# Mi2.net
KiCad netlist of a schematic drawn in EAGLE
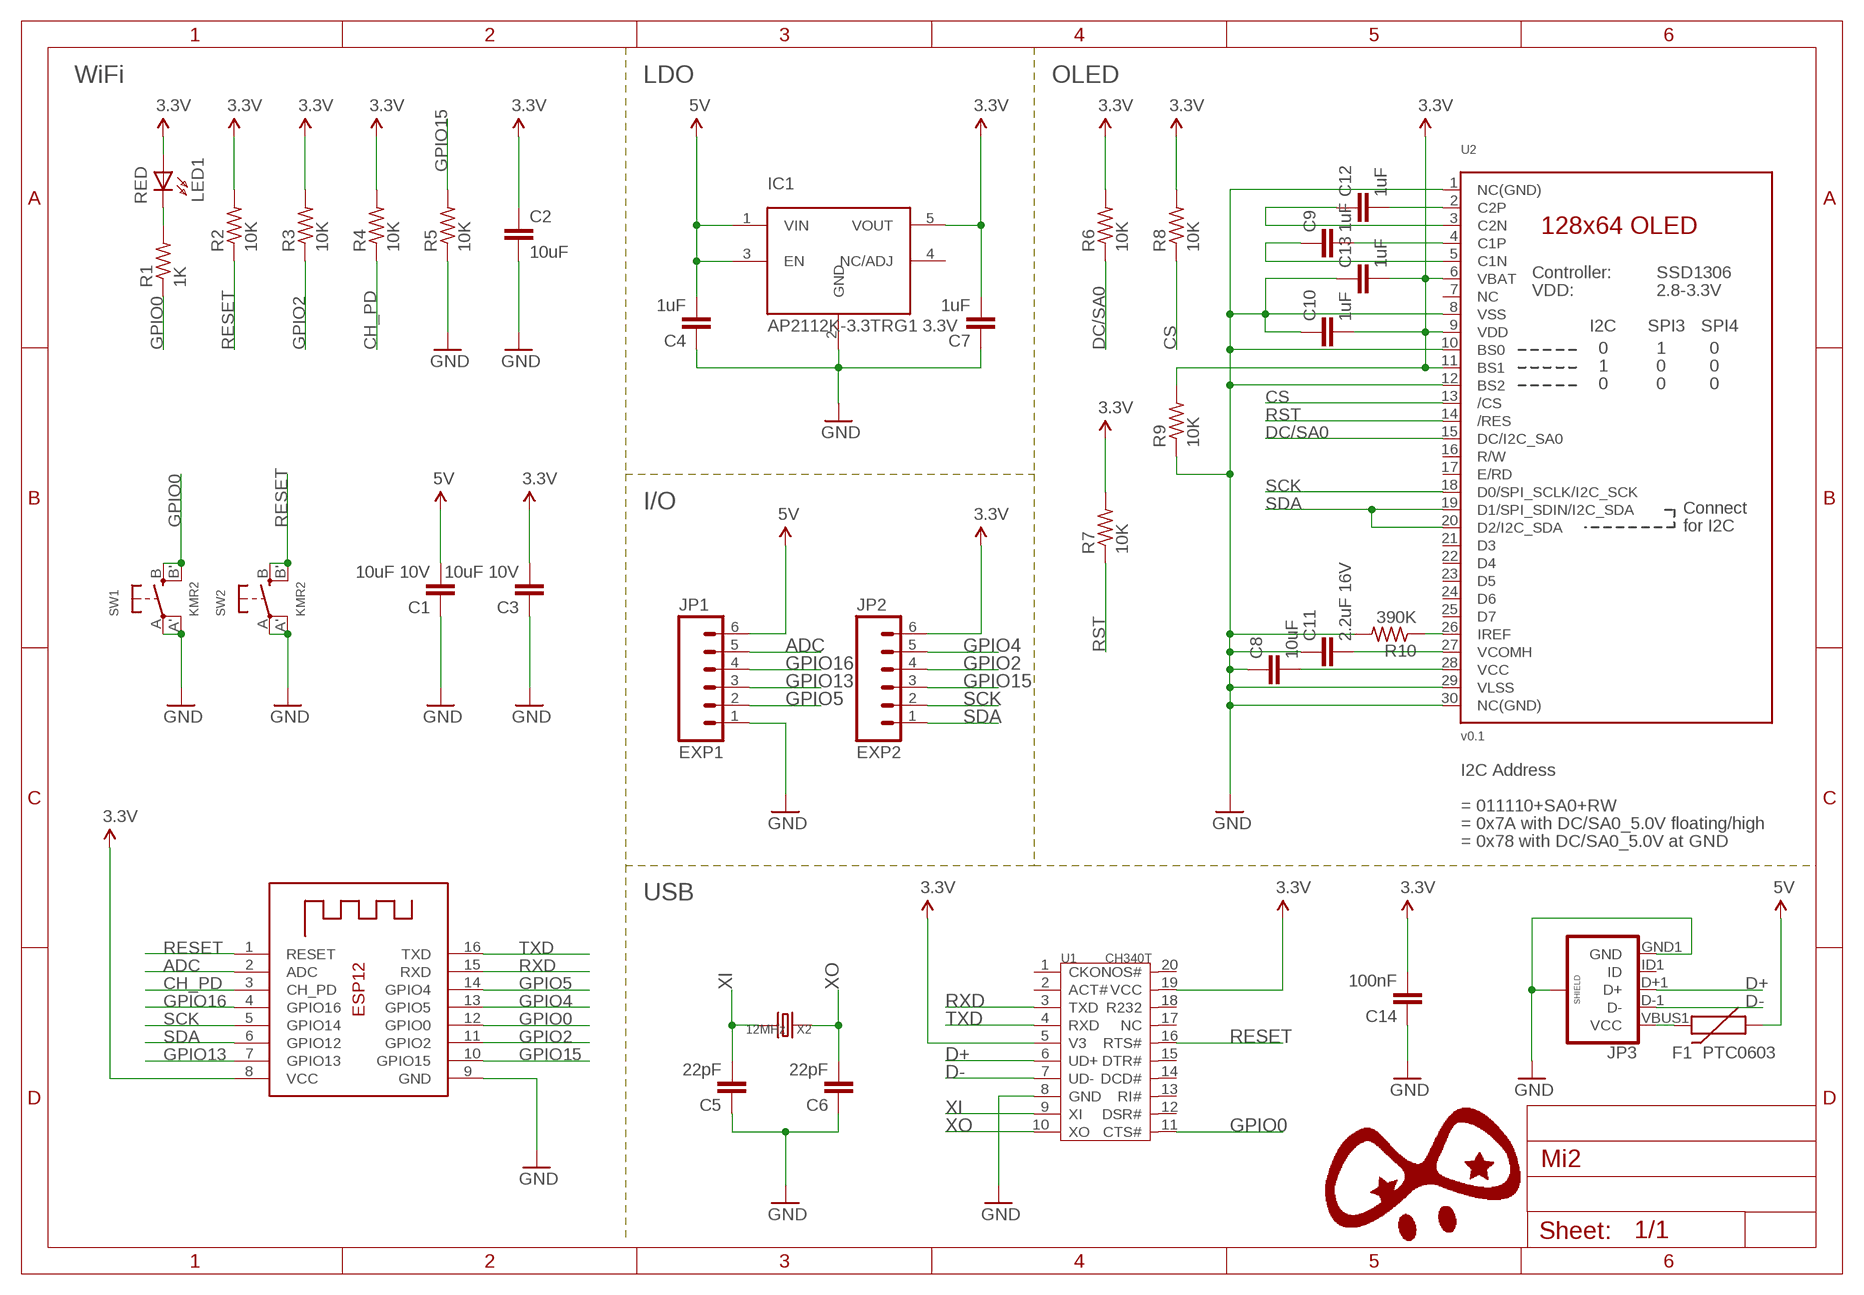
[diagram p0: schematic, sheet 1]

(export (version "E")
  (design (tool "Eeschema 10.0.6"))
  (components
    (comp (ref "C1")
      (value "10uF 10V")
      (footprint "eagle-import:0402-CAP")
      (libsource (lib "eagle-import") (part "CAP0402-CAP"))
    )
    (comp (ref "C2")
      (value "10uF")
      (footprint "eagle-import:0603-CAP")
      (libsource (lib "eagle-import") (part "10UF-6.3V-20%(0603)"))
    )
    (comp (ref "C3")
      (value "10uF 10V")
      (footprint "eagle-import:0402-CAP")
      (libsource (lib "eagle-import") (part "CAP0402-CAP"))
    )
    (comp (ref "C4")
      (value "1uF")
      (footprint "eagle-import:0402-CAP")
      (libsource (lib "eagle-import") (part "CAP0402-CAP"))
    )
    (comp (ref "C5")
      (value "22pF")
      (footprint "eagle-import:0402-CAP")
      (libsource (lib "eagle-import") (part "CAP0402-CAP"))
    )
    (comp (ref "C6")
      (value "22pF")
      (footprint "eagle-import:0402-CAP")
      (libsource (lib "eagle-import") (part "CAP0402-CAP"))
    )
    (comp (ref "C7")
      (value "1uF")
      (footprint "eagle-import:0402-CAP")
      (libsource (lib "eagle-import") (part "CAP0402-CAP"))
    )
    (comp (ref "C8")
      (value "10uF")
      (footprint "eagle-import:0603-CAP")
      (libsource (lib "eagle-import") (part "10UF-6.3V-20%(0603)"))
    )
    (comp (ref "C9")
      (value "1uF")
      (footprint "eagle-import:0603-CAP")
      (libsource (lib "eagle-import") (part "10UF-6.3V-20%(0603)"))
    )
    (comp (ref "C10")
      (value "1uF")
      (footprint "eagle-import:0603-CAP")
      (libsource (lib "eagle-import") (part "10UF-6.3V-20%(0603)"))
    )
    (comp (ref "C11")
      (value "2.2uF 16V")
      (footprint "eagle-import:0603-CAP")
      (libsource (lib "eagle-import") (part "10UF-6.3V-20%(0603)"))
    )
    (comp (ref "C12")
      (value "1uF")
      (footprint "eagle-import:0603-CAP")
      (libsource (lib "eagle-import") (part "10UF-6.3V-20%(0603)"))
    )
    (comp (ref "C13")
      (value "1uF")
      (footprint "eagle-import:0603-CAP")
      (libsource (lib "eagle-import") (part "10UF-6.3V-20%(0603)"))
    )
    (comp (ref "C14")
      (value "100nF")
      (footprint "eagle-import:0402-CAP")
      (libsource (lib "eagle-import") (part "CAP0402-CAP"))
    )
    (comp (ref "F1")
      (value "PTC0603")
      (footprint "eagle-import:0603")
      (libsource (lib "eagle-import") (part "PTC0603"))
    )
    (comp (ref "IC1")
      (value "AP2112K-3.3TRG1 3.3V")
      (footprint "eagle-import:SOT23-5")
      (libsource (lib "eagle-import") (part "5PIN_REG"))
    )
    (comp (ref "JP1")
      (value "EXP1")
      (footprint "eagle-import:1X06_LOCK")
      (libsource (lib "eagle-import") (part "M06LOCK"))
    )
    (comp (ref "JP2")
      (value "EXP2")
      (footprint "eagle-import:1X06_LOCK")
      (libsource (lib "eagle-import") (part "M06LOCK"))
    )
    (comp (ref "JP3")
      (value "USB_MICROB_PLUGCONN-11752")
      (footprint "eagle-import:USB-B-MICRO-SMD_V03")
      (libsource (lib "eagle-import") (part "USB_MICROB_PLUGCONN-11752"))
    )
    (comp (ref "LED1")
      (value "RED")
      (footprint "eagle-import:LED-0603_L")
      (libsource (lib "eagle-import") (part "LED0603DWS_L"))
    )
    (comp (ref "R1")
      (value "1K")
      (footprint "eagle-import:R0402")
      (libsource (lib "eagle-import") (part "R-US_R0402"))
    )
    (comp (ref "R2")
      (value "10K")
      (footprint "eagle-import:R0402")
      (libsource (lib "eagle-import") (part "R-US_R0402"))
    )
    (comp (ref "R3")
      (value "10K")
      (footprint "eagle-import:R0402")
      (libsource (lib "eagle-import") (part "R-US_R0402"))
    )
    (comp (ref "R4")
      (value "10K")
      (footprint "eagle-import:R0402")
      (libsource (lib "eagle-import") (part "R-US_R0402"))
    )
    (comp (ref "R5")
      (value "10K")
      (footprint "eagle-import:R0402")
      (libsource (lib "eagle-import") (part "R-US_R0402"))
    )
    (comp (ref "R6")
      (value "10K")
      (footprint "eagle-import:R0402")
      (libsource (lib "eagle-import") (part "R-US_R0402"))
    )
    (comp (ref "R7")
      (value "10K")
      (footprint "eagle-import:R0402")
      (libsource (lib "eagle-import") (part "R-US_R0402"))
    )
    (comp (ref "R8")
      (value "10K")
      (footprint "eagle-import:R0402")
      (libsource (lib "eagle-import") (part "R-US_R0402"))
    )
    (comp (ref "R9")
      (value "10K")
      (footprint "eagle-import:R0402")
      (libsource (lib "eagle-import") (part "R-US_R0402"))
    )
    (comp (ref "R10")
      (value "390K")
      (footprint "eagle-import:R0402")
      (libsource (lib "eagle-import") (part "R-US_R0402"))
    )
    (comp (ref "SW1")
      (value "KMR2")
      (footprint "eagle-import:BTN_KMR2_4.6X2.8")
      (libsource (lib "eagle-import") (part "SWITCH_TACT_SMT4.6X2.8"))
    )
    (comp (ref "SW2")
      (value "KMR2")
      (footprint "eagle-import:BTN_KMR2_4.6X2.8")
      (libsource (lib "eagle-import") (part "SWITCH_TACT_SMT4.6X2.8"))
    )
    (comp (ref "U1")
      (value "CH340T")
      (footprint "eagle-import:SSOP20")
      (libsource (lib "eagle-import") (part "CH340T"))
    )
    (comp (ref "U2")
      (value "v0.1")
      (footprint "eagle-import:UG-2864HSWEG01_0.96IN_WRAPAROUND")
      (libsource (lib "eagle-import") (part "DISP_OLED_UG-2864HSWEG010.96{dblquote}"))
    )
    (comp (ref "X1")
      (value "ESP-12")
      (footprint "eagle-import:ESP-12")
      (libsource (lib "eagle-import") (part "ESP-12"))
    )
    (comp (ref "X2")
      (value "12MHz")
      (footprint "eagle-import:2P-SMD-5X3.2")
      (libsource (lib "eagle-import") (part "CRYSTAL'5032'"))
    )
  )
  (nets
    (net (code "1") (name "/ADC") (class "Default")
      (node (ref "JP1") (pin "5") (pinfunction "5_5") (pintype "passive"))
      (node (ref "X1") (pin "2") (pinfunction "ADC_2") (pintype "passive"))
    )
    (net (code "2") (name "/CH_PD") (class "Default")
      (node (ref "R4") (pin "1") (pinfunction "1_1") (pintype "passive"))
      (node (ref "X1") (pin "3") (pinfunction "CH_PD_3") (pintype "input"))
    )
    (net (code "3") (name "/CS") (class "Default")
      (node (ref "R8") (pin "1") (pinfunction "1_1") (pintype "passive"))
      (node (ref "U2") (pin "13") (pinfunction "/CS_13") (pintype "input"))
    )
    (net (code "4") (name "/D+") (class "Default")
      (node (ref "JP3") (pin "D+1") (pinfunction "D+_D+1") (pintype "bidirectional"))
      (node (ref "U1") (pin "6") (pinfunction "UD+_6") (pintype "bidirectional"))
    )
    (net (code "5") (name "/D-") (class "Default")
      (node (ref "JP3") (pin "D-1") (pinfunction "D-_D-1") (pintype "bidirectional"))
      (node (ref "U1") (pin "7") (pinfunction "UD-_7") (pintype "bidirectional"))
    )
    (net (code "6") (name "/DC{slash}SA0") (class "Default")
      (node (ref "R6") (pin "1") (pinfunction "1_1") (pintype "passive"))
      (node (ref "U2") (pin "15") (pinfunction "DC/I2C_SA0_15") (pintype "input"))
    )
    (net (code "7") (name "/GPIO0") (class "Default")
      (node (ref "R1") (pin "1") (pinfunction "1_1") (pintype "passive"))
      (node (ref "SW1") (pin "B") (pinfunction "S_B") (pintype "passive"))
      (node (ref "SW1") (pin "B'") (pinfunction "S1_B'") (pintype "passive"))
      (node (ref "U1") (pin "11") (pinfunction "CTS#_11") (pintype "input"))
      (node (ref "X1") (pin "12") (pinfunction "GPIO0_12") (pintype "bidirectional"))
    )
    (net (code "8") (name "/GPIO2") (class "Default")
      (node (ref "JP2") (pin "4") (pinfunction "4_4") (pintype "passive"))
      (node (ref "R3") (pin "1") (pinfunction "1_1") (pintype "passive"))
      (node (ref "X1") (pin "11") (pinfunction "GPIO2_11") (pintype "bidirectional"))
    )
    (net (code "9") (name "/GPIO4") (class "Default")
      (node (ref "JP2") (pin "5") (pinfunction "5_5") (pintype "passive"))
      (node (ref "X1") (pin "13") (pinfunction "GPIO5_13") (pintype "bidirectional"))
    )
    (net (code "10") (name "/GPIO5") (class "Default")
      (node (ref "JP1") (pin "2") (pinfunction "2_2") (pintype "passive"))
      (node (ref "X1") (pin "14") (pinfunction "GPIO4_14") (pintype "bidirectional"))
    )
    (net (code "11") (name "/GPIO13") (class "Default")
      (node (ref "JP1") (pin "3") (pinfunction "3_3") (pintype "passive"))
      (node (ref "X1") (pin "7") (pinfunction "GPIO13_7") (pintype "bidirectional"))
    )
    (net (code "12") (name "/GPIO15") (class "Default")
      (node (ref "JP2") (pin "3") (pinfunction "3_3") (pintype "passive"))
      (node (ref "R5") (pin "2") (pinfunction "2_2") (pintype "passive"))
      (node (ref "X1") (pin "10") (pinfunction "GPIO15_10") (pintype "bidirectional"))
    )
    (net (code "13") (name "/GPIO16") (class "Default")
      (node (ref "JP1") (pin "4") (pinfunction "4_4") (pintype "passive"))
      (node (ref "X1") (pin "4") (pinfunction "GPIO16_4") (pintype "bidirectional"))
    )
    (net (code "14") (name "/NOS#") (class "Default")
      (node (ref "U1") (pin "20") (pinfunction "NOS#_20") (pintype "power_in"))
    )
    (net (code "15") (name "/RESET") (class "Default")
      (node (ref "R2") (pin "1") (pinfunction "1_1") (pintype "passive"))
      (node (ref "SW2") (pin "B") (pinfunction "S_B") (pintype "passive"))
      (node (ref "SW2") (pin "B'") (pinfunction "S1_B'") (pintype "passive"))
      (node (ref "U1") (pin "16") (pinfunction "RTS#_16") (pintype "output"))
      (node (ref "X1") (pin "1") (pinfunction "RESET_1") (pintype "input"))
    )
    (net (code "16") (name "/RST") (class "Default")
      (node (ref "R7") (pin "1") (pinfunction "1_1") (pintype "passive"))
      (node (ref "U2") (pin "14") (pinfunction "/RES_14") (pintype "input"))
    )
    (net (code "17") (name "/RXD") (class "Default")
      (node (ref "U1") (pin "3") (pinfunction "TXD_3") (pintype "output"))
      (node (ref "X1") (pin "15") (pinfunction "RXD_15") (pintype "input"))
    )
    (net (code "18") (name "/SCK") (class "Default")
      (node (ref "JP2") (pin "2") (pinfunction "2_2") (pintype "passive"))
      (node (ref "U2") (pin "18") (pinfunction "D0/SPI_SCLK/I2C_SCK_18") (pintype "bidirectional"))
      (node (ref "X1") (pin "5") (pinfunction "GPIO14_5") (pintype "bidirectional"))
    )
    (net (code "19") (name "/SDA") (class "Default")
      (node (ref "JP2") (pin "1") (pinfunction "1_1") (pintype "passive"))
      (node (ref "U2") (pin "19") (pinfunction "D1/SPI_SDIN/I2C_SDA_19") (pintype "bidirectional"))
      (node (ref "U2") (pin "20") (pinfunction "D2/I2C_SDA_20") (pintype "bidirectional"))
      (node (ref "X1") (pin "6") (pinfunction "GPIO12_6") (pintype "bidirectional"))
    )
    (net (code "20") (name "/TXD") (class "Default")
      (node (ref "U1") (pin "4") (pinfunction "RXD_4") (pintype "input"))
      (node (ref "X1") (pin "16") (pinfunction "TXD_16") (pintype "output"))
    )
    (net (code "21") (name "/XI") (class "Default")
      (node (ref "C5") (pin "2") (pinfunction "2_2") (pintype "passive"))
      (node (ref "U1") (pin "9") (pinfunction "XI_9") (pintype "input"))
      (node (ref "X2") (pin "2") (pinfunction "2_2") (pintype "passive"))
    )
    (net (code "22") (name "/XO") (class "Default")
      (node (ref "C6") (pin "2") (pinfunction "2_2") (pintype "passive"))
      (node (ref "U1") (pin "10") (pinfunction "XO_10") (pintype "output"))
      (node (ref "X2") (pin "1") (pinfunction "1_1") (pintype "passive"))
    )
    (net (code "23") (name "3.3V") (class "Default")
      (node (ref "C10") (pin "2") (pinfunction "2_2") (pintype "passive"))
      (node (ref "C13") (pin "2") (pinfunction "2_2") (pintype "passive"))
      (node (ref "C14") (pin "2") (pinfunction "2_2") (pintype "passive"))
      (node (ref "C2") (pin "1") (pinfunction "1_1") (pintype "passive"))
      (node (ref "C3") (pin "2") (pinfunction "2_2") (pintype "passive"))
      (node (ref "C7") (pin "2") (pinfunction "2_2") (pintype "passive"))
      (node (ref "IC1") (pin "5") (pinfunction "VOUT_5") (pintype "bidirectional"))
      (node (ref "JP2") (pin "6") (pinfunction "6_6") (pintype "passive"))
      (node (ref "LED1") (pin "A") (pinfunction "A_A") (pintype "passive"))
      (node (ref "R2") (pin "2") (pinfunction "2_2") (pintype "passive"))
      (node (ref "R3") (pin "2") (pinfunction "2_2") (pintype "passive"))
      (node (ref "R4") (pin "2") (pinfunction "2_2") (pintype "passive"))
      (node (ref "R6") (pin "2") (pinfunction "2_2") (pintype "passive"))
      (node (ref "R7") (pin "2") (pinfunction "2_2") (pintype "passive"))
      (node (ref "R8") (pin "2") (pinfunction "2_2") (pintype "passive"))
      (node (ref "R9") (pin "2") (pinfunction "2_2") (pintype "passive"))
      (node (ref "U1") (pin "19") (pinfunction "VCC_19") (pintype "power_in"))
      (node (ref "U1") (pin "5") (pinfunction "V3_5") (pintype "power_in"))
      (node (ref "U2") (pin "11") (pinfunction "BS1_11") (pintype "input"))
      (node (ref "U2") (pin "6") (pinfunction "VBAT_6") (pintype "input"))
      (node (ref "U2") (pin "9") (pinfunction "VDD_9") (pintype "power_in"))
      (node (ref "X1") (pin "8") (pinfunction "VCC_8") (pintype "power_in"))
    )
    (net (code "24") (name "5V") (class "Default")
      (node (ref "C1") (pin "2") (pinfunction "2_2") (pintype "passive"))
      (node (ref "C4") (pin "2") (pinfunction "2_2") (pintype "passive"))
      (node (ref "F1") (pin "1") (pinfunction "1_1") (pintype "bidirectional"))
      (node (ref "IC1") (pin "1") (pinfunction "VIN_1") (pintype "bidirectional"))
      (node (ref "IC1") (pin "3") (pinfunction "EN_3") (pintype "bidirectional"))
      (node (ref "JP1") (pin "6") (pinfunction "6_6") (pintype "passive"))
    )
    (net (code "25") (name "GND") (class "Default")
      (node (ref "C1") (pin "1") (pinfunction "1_1") (pintype "passive"))
      (node (ref "C10") (pin "1") (pinfunction "1_1") (pintype "passive"))
      (node (ref "C11") (pin "1") (pinfunction "1_1") (pintype "passive"))
      (node (ref "C13") (pin "1") (pinfunction "1_1") (pintype "passive"))
      (node (ref "C14") (pin "1") (pinfunction "1_1") (pintype "passive"))
      (node (ref "C2") (pin "2") (pinfunction "2_2") (pintype "passive"))
      (node (ref "C3") (pin "1") (pinfunction "1_1") (pintype "passive"))
      (node (ref "C4") (pin "1") (pinfunction "1_1") (pintype "passive"))
      (node (ref "C5") (pin "1") (pinfunction "1_1") (pintype "passive"))
      (node (ref "C6") (pin "1") (pinfunction "1_1") (pintype "passive"))
      (node (ref "C7") (pin "1") (pinfunction "1_1") (pintype "passive"))
      (node (ref "C8") (pin "1") (pinfunction "1_1") (pintype "passive"))
      (node (ref "IC1") (pin "2") (pinfunction "GND_2") (pintype "bidirectional"))
      (node (ref "JP1") (pin "1") (pinfunction "1_1") (pintype "passive"))
      (node (ref "JP3") (pin "GND1") (pinfunction "GND_GND1") (pintype "bidirectional"))
      (node (ref "JP3") (pin "SHIELD1") (pinfunction "SHIELD_SHIELD1") (pintype "bidirectional"))
      (node (ref "JP3") (pin "SHIELD2") (pinfunction "SHIELD_SHIELD2") (pintype "bidirectional"))
      (node (ref "JP3") (pin "SHIELD3") (pinfunction "SHIELD_SHIELD3") (pintype "bidirectional"))
      (node (ref "R10") (pin "2") (pinfunction "2_2") (pintype "passive"))
      (node (ref "R5") (pin "1") (pinfunction "1_1") (pintype "passive"))
      (node (ref "R9") (pin "1") (pinfunction "1_1") (pintype "passive"))
      (node (ref "SW1") (pin "A") (pinfunction "P_A") (pintype "passive"))
      (node (ref "SW1") (pin "A'") (pinfunction "P1_A'") (pintype "passive"))
      (node (ref "SW2") (pin "A") (pinfunction "P_A") (pintype "passive"))
      (node (ref "SW2") (pin "A'") (pinfunction "P1_A'") (pintype "passive"))
      (node (ref "U1") (pin "8") (pinfunction "GND_8") (pintype "power_in"))
      (node (ref "U2") (pin "1") (pinfunction "NC(GND)_1") (pintype "input"))
      (node (ref "U2") (pin "10") (pinfunction "BS0_10") (pintype "input"))
      (node (ref "U2") (pin "12") (pinfunction "BS2_12") (pintype "input"))
      (node (ref "U2") (pin "29") (pinfunction "VLSS_29") (pintype "power_in"))
      (node (ref "U2") (pin "30") (pinfunction "NC(GND)_30") (pintype "input"))
      (node (ref "U2") (pin "8") (pinfunction "VSS_8") (pintype "power_in"))
      (node (ref "X1") (pin "9") (pinfunction "GND_9") (pintype "power_in"))
    )
    (net (code "26") (name "Net-(JP3-VCC)") (class "Default")
      (node (ref "F1") (pin "2") (pinfunction "2_2") (pintype "bidirectional"))
      (node (ref "JP3") (pin "VBUS1") (pinfunction "VCC_VBUS1") (pintype "bidirectional"))
    )
    (net (code "27") (name "Net-(LED1-PadC)") (class "Default")
      (node (ref "LED1") (pin "C") (pinfunction "C_C") (pintype "passive"))
      (node (ref "R1") (pin "2") (pinfunction "2_2") (pintype "passive"))
    )
    (net (code "28") (name "Net-(U2-C1N)") (class "Default")
      (node (ref "C9") (pin "1") (pinfunction "1_1") (pintype "passive"))
      (node (ref "U2") (pin "5") (pinfunction "C1N_5") (pintype "input"))
    )
    (net (code "29") (name "Net-(U2-C1P)") (class "Default")
      (node (ref "C9") (pin "2") (pinfunction "2_2") (pintype "passive"))
      (node (ref "U2") (pin "4") (pinfunction "C1P_4") (pintype "input"))
    )
    (net (code "30") (name "Net-(U2-C2N)") (class "Default")
      (node (ref "C12") (pin "1") (pinfunction "1_1") (pintype "passive"))
      (node (ref "U2") (pin "3") (pinfunction "C2N_3") (pintype "input"))
    )
    (net (code "31") (name "Net-(U2-C2P)") (class "Default")
      (node (ref "C12") (pin "2") (pinfunction "2_2") (pintype "passive"))
      (node (ref "U2") (pin "2") (pinfunction "C2P_2") (pintype "input"))
    )
    (net (code "32") (name "Net-(U2-IREF)") (class "Default")
      (node (ref "R10") (pin "1") (pinfunction "1_1") (pintype "passive"))
      (node (ref "U2") (pin "26") (pinfunction "IREF_26") (pintype "input"))
    )
    (net (code "33") (name "Net-(U2-VCC)") (class "Default")
      (node (ref "C8") (pin "2") (pinfunction "2_2") (pintype "passive"))
      (node (ref "U2") (pin "28") (pinfunction "VCC_28") (pintype "power_in"))
    )
    (net (code "34") (name "Net-(U2-VCOMH)") (class "Default")
      (node (ref "C11") (pin "2") (pinfunction "2_2") (pintype "passive"))
      (node (ref "U2") (pin "27") (pinfunction "VCOMH_27") (pintype "output"))
    )
    (net (code "35") (name "unconnected-(IC1-NC{slash}ADJ-Pad4)") (class "Default")
      (node (ref "IC1") (pin "4") (pinfunction "NC/ADJ_4") (pintype "bidirectional"))
    )
    (net (code "36") (name "unconnected-(JP3-ID-PadID1)") (class "Default")
      (node (ref "JP3") (pin "ID1") (pinfunction "ID_ID1") (pintype "bidirectional"))
    )
    (net (code "37") (name "unconnected-(U1-ACT#-Pad2)") (class "Default")
      (node (ref "U1") (pin "2") (pinfunction "ACT#_2") (pintype "output"))
    )
    (net (code "38") (name "unconnected-(U1-CKO-Pad1)") (class "Default")
      (node (ref "U1") (pin "1") (pinfunction "CKO_1") (pintype "output"))
    )
    (net (code "39") (name "unconnected-(U1-DCD#-Pad14)") (class "Default")
      (node (ref "U1") (pin "14") (pinfunction "DCD#_14") (pintype "input"))
    )
    (net (code "40") (name "unconnected-(U1-DSR#-Pad12)") (class "Default")
      (node (ref "U1") (pin "12") (pinfunction "DSR#_12") (pintype "input"))
    )
    (net (code "41") (name "unconnected-(U1-DTR#-Pad15)") (class "Default")
      (node (ref "U1") (pin "15") (pinfunction "DTR#_15") (pintype "output"))
    )
    (net (code "42") (name "unconnected-(U1-NC-Pad17)") (class "Default")
      (node (ref "U1") (pin "17") (pinfunction "NC_17") (pintype "no_connect"))
    )
    (net (code "43") (name "unconnected-(U1-R232-Pad18)") (class "Default")
      (node (ref "U1") (pin "18") (pinfunction "R232_18") (pintype "input"))
    )
    (net (code "44") (name "unconnected-(U1-RI#-Pad13)") (class "Default")
      (node (ref "U1") (pin "13") (pinfunction "RI#_13") (pintype "input"))
    )
    (net (code "45") (name "unconnected-(U2-D3-Pad21)") (class "Default")
      (node (ref "U2") (pin "21") (pinfunction "D3_21") (pintype "bidirectional"))
    )
    (net (code "46") (name "unconnected-(U2-D4-Pad22)") (class "Default")
      (node (ref "U2") (pin "22") (pinfunction "D4_22") (pintype "bidirectional"))
    )
    (net (code "47") (name "unconnected-(U2-D5-Pad23)") (class "Default")
      (node (ref "U2") (pin "23") (pinfunction "D5_23") (pintype "bidirectional"))
    )
    (net (code "48") (name "unconnected-(U2-D6-Pad24)") (class "Default")
      (node (ref "U2") (pin "24") (pinfunction "D6_24") (pintype "bidirectional"))
    )
    (net (code "49") (name "unconnected-(U2-D7-Pad25)") (class "Default")
      (node (ref "U2") (pin "25") (pinfunction "D7_25") (pintype "bidirectional"))
    )
    (net (code "50") (name "unconnected-(U2-E{slash}RD-Pad17)") (class "Default")
      (node (ref "U2") (pin "17") (pinfunction "E/RD_17") (pintype "input"))
    )
    (net (code "51") (name "unconnected-(U2-NC-Pad7)") (class "Default")
      (node (ref "U2") (pin "7") (pinfunction "NC_7") (pintype "no_connect"))
    )
    (net (code "52") (name "unconnected-(U2-R{slash}W-Pad16)") (class "Default")
      (node (ref "U2") (pin "16") (pinfunction "R/W_16") (pintype "input"))
    )
  )
)
